# door-lock-pcb.net
KiCad netlist of a schematic drawn in EAGLE
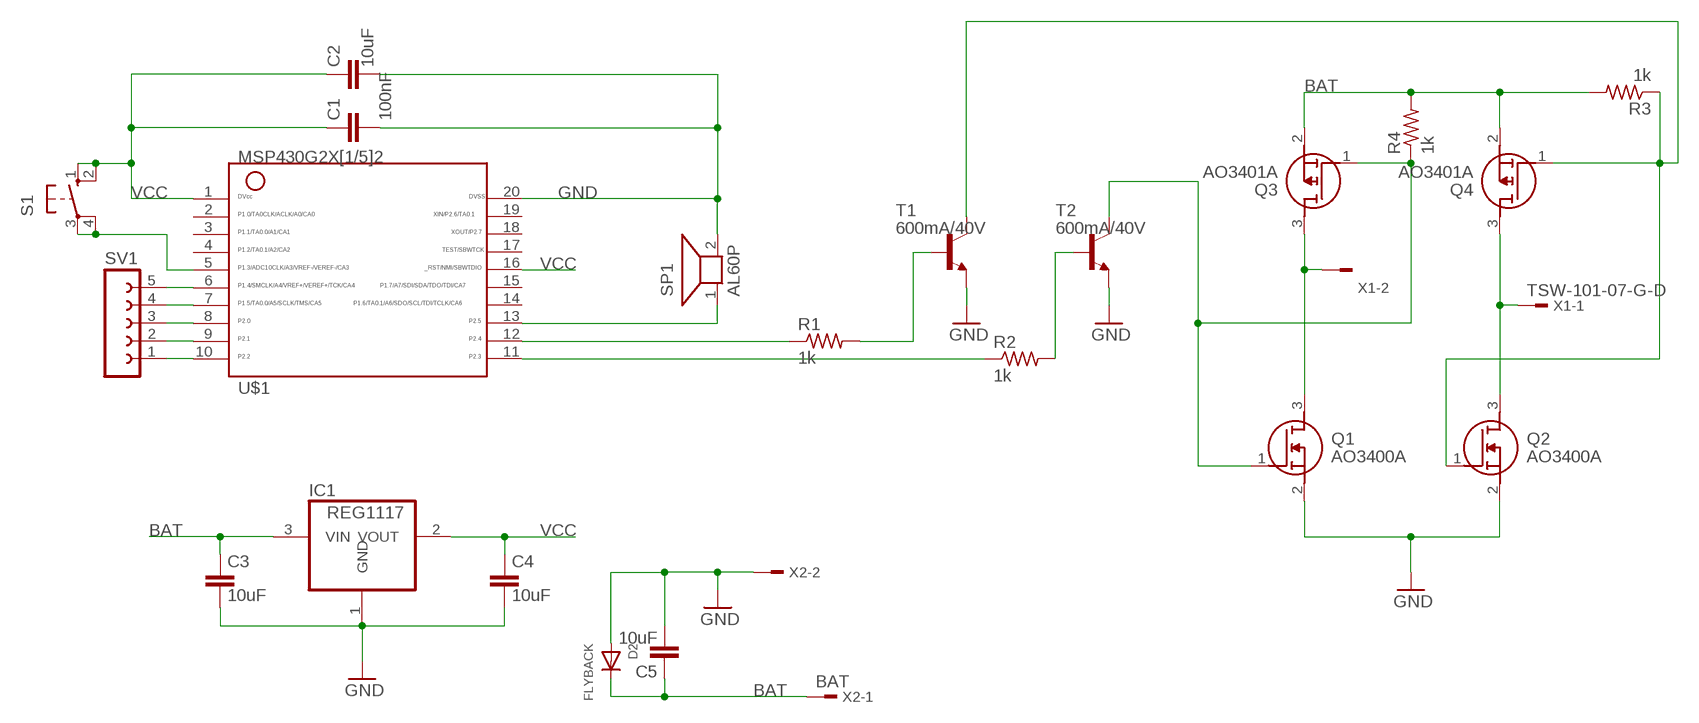
[diagram p0: schematic, sheet 1]

(export (version "E")
  (design (tool "Eeschema 10.0.6"))
  (components
    (comp (ref "C1")
      (value "100nF")
      (footprint "eagle-import:CAP_0805")
      (fields
        (field (name "DIGIKEY_PART_NUMBER") "311-1140-2-ND")
        (field (name "MANUFACTURER") "Yageo")
        (field (name "MPN") "CC0805KRX7R9BB104")
        (field (name "CREATED_BY") "PCBLayout.com")
      )
      (libsource (lib "eagle-import") (part "CC0805KRX7R9BB104"))
    )
    (comp (ref "C2")
      (value "10uF")
      (footprint "eagle-import:CAP_0805")
      (fields
        (field (name "DIGIKEY_PART_NUMBER") "311-1140-2-ND")
        (field (name "MANUFACTURER") "Yageo")
        (field (name "MPN") "CC0805KRX7R9BB104")
        (field (name "CREATED_BY") "PCBLayout.com")
      )
      (libsource (lib "eagle-import") (part "CC0805KRX7R9BB104"))
    )
    (comp (ref "C3")
      (value "10uF")
      (footprint "eagle-import:CAP_0805")
      (fields
        (field (name "DIGIKEY_PART_NUMBER") "311-1140-2-ND")
        (field (name "MANUFACTURER") "Yageo")
        (field (name "MPN") "CC0805KRX7R9BB104")
        (field (name "CREATED_BY") "PCBLayout.com")
      )
      (libsource (lib "eagle-import") (part "CC0805KRX7R9BB104"))
    )
    (comp (ref "C4")
      (value "10uF")
      (footprint "eagle-import:CAP_0805")
      (fields
        (field (name "DIGIKEY_PART_NUMBER") "311-1140-2-ND")
        (field (name "MANUFACTURER") "Yageo")
        (field (name "MPN") "CC0805KRX7R9BB104")
        (field (name "CREATED_BY") "PCBLayout.com")
      )
      (libsource (lib "eagle-import") (part "CC0805KRX7R9BB104"))
    )
    (comp (ref "C5")
      (value "10uF")
      (footprint "eagle-import:CAP_0805")
      (fields
        (field (name "DIGIKEY_PART_NUMBER") "311-1140-2-ND")
        (field (name "MANUFACTURER") "Yageo")
        (field (name "MPN") "CC0805KRX7R9BB104")
        (field (name "CREATED_BY") "PCBLayout.com")
      )
      (libsource (lib "eagle-import") (part "CC0805KRX7R9BB104"))
    )
    (comp (ref "D2")
      (value "FLYBACK")
      (footprint "eagle-import:SOD-523")
      (libsource (lib "eagle-import") (part "DIODESOD-523"))
    )
    (comp (ref "IC1")
      (value "REG1117")
      (footprint "eagle-import:SOT223")
      (libsource (lib "eagle-import") (part "REG1117"))
    )
    (comp (ref "Q1")
      (value "AO3400A")
      (footprint "eagle-import:SOT95P280X125-3N")
      (libsource (lib "eagle-import") (part "AO3400A"))
    )
    (comp (ref "Q2")
      (value "AO3400A")
      (footprint "eagle-import:SOT95P280X125-3N")
      (libsource (lib "eagle-import") (part "AO3400A"))
    )
    (comp (ref "Q3")
      (value "AO3401A")
      (footprint "eagle-import:SOT95P280X125-3N")
      (libsource (lib "eagle-import") (part "AO3401A"))
    )
    (comp (ref "Q4")
      (value "AO3401A")
      (footprint "eagle-import:SOT95P280X125-3N")
      (libsource (lib "eagle-import") (part "AO3401A"))
    )
    (comp (ref "R1")
      (value "1k")
      (footprint "eagle-import:RES_0805")
      (fields
        (field (name "DIGIKEY_PART_NUMBER") "541-0.0ATR-ND")
        (field (name "MANUFACTURER") "Vishay Dale")
        (field (name "MPN") "CRCW08050000Z0EA")
        (field (name "CREATED_BY") "PCBLayout.com")
      )
      (libsource (lib "eagle-import") (part "CRCW08050000Z0EA"))
    )
    (comp (ref "R2")
      (value "1k")
      (footprint "eagle-import:RES_0805")
      (fields
        (field (name "DIGIKEY_PART_NUMBER") "541-0.0ATR-ND")
        (field (name "MANUFACTURER") "Vishay Dale")
        (field (name "MPN") "CRCW08050000Z0EA")
        (field (name "CREATED_BY") "PCBLayout.com")
      )
      (libsource (lib "eagle-import") (part "CRCW08050000Z0EA"))
    )
    (comp (ref "R3")
      (value "1k")
      (footprint "eagle-import:RES_0805")
      (fields
        (field (name "DIGIKEY_PART_NUMBER") "541-0.0ATR-ND")
        (field (name "MANUFACTURER") "Vishay Dale")
        (field (name "MPN") "CRCW08050000Z0EA")
        (field (name "CREATED_BY") "PCBLayout.com")
      )
      (libsource (lib "eagle-import") (part "CRCW08050000Z0EA"))
    )
    (comp (ref "R4")
      (value "1k")
      (footprint "eagle-import:RES_0805")
      (fields
        (field (name "DIGIKEY_PART_NUMBER") "541-0.0ATR-ND")
        (field (name "MANUFACTURER") "Vishay Dale")
        (field (name "MPN") "CRCW08050000Z0EA")
        (field (name "CREATED_BY") "PCBLayout.com")
      )
      (libsource (lib "eagle-import") (part "CRCW08050000Z0EA"))
    )
    (comp (ref "S1")
      (value "10-XX")
      (footprint "eagle-import:B3F-10XX")
      (fields (field (name "MPN") "B3F-1000"))
      (libsource (lib "eagle-import") (part "10-XX"))
    )
    (comp (ref "SP1")
      (value "AL60P")
      (footprint "eagle-import:AL60P")
      (libsource (lib "eagle-import") (part "AL60P"))
    )
    (comp (ref "SV1")
      (value "FE05-1")
      (footprint "eagle-import:FE05-1")
      (libsource (lib "eagle-import") (part "FE05-1"))
    )
    (comp (ref "T1")
      (value "600mA/40V")
      (footprint "eagle-import:SOT23-3")
      (libsource (lib "eagle-import") (part "TRANS_NPN-MMBT2222AL"))
    )
    (comp (ref "T2")
      (value "600mA/40V")
      (footprint "eagle-import:SOT23-3")
      (libsource (lib "eagle-import") (part "TRANS_NPN-MMBT2222AL"))
    )
    (comp (ref "U$1")
      (value "G2X[1/5]2---N20")
      (footprint "eagle-import:N20")
      (libsource (lib "eagle-import") (part "G2X[1/5]2---N20"))
    )
    (comp (ref "X1")
      (value "TSW-101-07-G-D")
      (footprint "eagle-import:TSW-101-XX-G-D")
      (fields (field (name "MF") "Samtec Inc."))
      (libsource (lib "eagle-import") (part "TSW-101--G-D07"))
    )
    (comp (ref "X2")
      (value "BAT")
      (footprint "eagle-import:TSW-101-XX-G-D")
      (fields (field (name "MF") "Samtec Inc.") (field (name "MPN") "TSW-101-07-G-D"))
      (libsource (lib "eagle-import") (part "TSW-101--G-D07"))
    )
  )
  (nets
    (net (code "1") (name "/BAT") (class "Default")
      (node (ref "C3") (pin "1") (pinfunction "1_1") (pintype "passive"))
      (node (ref "C5") (pin "1") (pinfunction "1_1") (pintype "passive"))
      (node (ref "D2") (pin "K") (pinfunction "C_K") (pintype "passive"))
      (node (ref "IC1") (pin "3") (pinfunction "VIN_3") (pintype "input"))
      (node (ref "Q3") (pin "2") (pinfunction "S_2") (pintype "bidirectional"))
      (node (ref "Q4") (pin "2") (pinfunction "S_2") (pintype "bidirectional"))
      (node (ref "R3") (pin "2") (pinfunction "2_2") (pintype "passive"))
      (node (ref "R4") (pin "2") (pinfunction "2_2") (pintype "passive"))
      (node (ref "X2") (pin "1") (pinfunction "1_1") (pintype "passive"))
    )
    (net (code "2") (name "/VCC") (class "Default")
      (node (ref "C1") (pin "1") (pinfunction "1_1") (pintype "passive"))
      (node (ref "C2") (pin "1") (pinfunction "1_1") (pintype "passive"))
      (node (ref "C4") (pin "1") (pinfunction "1_1") (pintype "passive"))
      (node (ref "IC1") (pin "2") (pinfunction "VOUT_2") (pintype "output"))
      (node (ref "S1") (pin "1") (pinfunction "S_1") (pintype "passive"))
      (node (ref "S1") (pin "2") (pinfunction "S1_2") (pintype "passive"))
      (node (ref "U$1") (pin "1") (pinfunction "1_1") (pintype "bidirectional"))
      (node (ref "U$1") (pin "16") (pinfunction "16_16") (pintype "bidirectional"))
    )
    (net (code "3") (name "GND") (class "Default")
      (node (ref "C1") (pin "2") (pinfunction "2_2") (pintype "passive"))
      (node (ref "C2") (pin "2") (pinfunction "2_2") (pintype "passive"))
      (node (ref "C3") (pin "2") (pinfunction "2_2") (pintype "passive"))
      (node (ref "C4") (pin "2") (pinfunction "2_2") (pintype "passive"))
      (node (ref "C5") (pin "2") (pinfunction "2_2") (pintype "passive"))
      (node (ref "D2") (pin "A") (pinfunction "A_A") (pintype "passive"))
      (node (ref "IC1") (pin "1") (pinfunction "GND_1") (pintype "power_in"))
      (node (ref "Q1") (pin "2") (pinfunction "S_2") (pintype "bidirectional"))
      (node (ref "Q2") (pin "2") (pinfunction "S_2") (pintype "bidirectional"))
      (node (ref "SP1") (pin "2") (pinfunction "2_2") (pintype "passive"))
      (node (ref "T1") (pin "2") (pinfunction "E_2") (pintype "passive"))
      (node (ref "T2") (pin "2") (pinfunction "E_2") (pintype "passive"))
      (node (ref "U$1") (pin "20") (pinfunction "20_20") (pintype "bidirectional"))
      (node (ref "X2") (pin "2") (pinfunction "1_2") (pintype "passive"))
    )
    (net (code "4") (name "Net-(Q1-D)") (class "Default")
      (node (ref "Q1") (pin "3") (pinfunction "D_3") (pintype "bidirectional"))
      (node (ref "Q3") (pin "3") (pinfunction "D_3") (pintype "bidirectional"))
      (node (ref "X1") (pin "2") (pinfunction "1_2") (pintype "passive"))
    )
    (net (code "5") (name "Net-(Q1-G)") (class "Default")
      (node (ref "Q1") (pin "1") (pinfunction "G_1") (pintype "bidirectional"))
      (node (ref "Q3") (pin "1") (pinfunction "G_1") (pintype "bidirectional"))
      (node (ref "R4") (pin "1") (pinfunction "1_1") (pintype "passive"))
      (node (ref "T2") (pin "3") (pinfunction "C_3") (pintype "passive"))
    )
    (net (code "6") (name "Net-(Q2-D)") (class "Default")
      (node (ref "Q2") (pin "3") (pinfunction "D_3") (pintype "bidirectional"))
      (node (ref "Q4") (pin "3") (pinfunction "D_3") (pintype "bidirectional"))
      (node (ref "X1") (pin "1") (pinfunction "1_1") (pintype "passive"))
    )
    (net (code "7") (name "Net-(Q2-G)") (class "Default")
      (node (ref "Q2") (pin "1") (pinfunction "G_1") (pintype "bidirectional"))
      (node (ref "Q4") (pin "1") (pinfunction "G_1") (pintype "bidirectional"))
      (node (ref "R3") (pin "1") (pinfunction "1_1") (pintype "passive"))
      (node (ref "T1") (pin "3") (pinfunction "C_3") (pintype "passive"))
    )
    (net (code "8") (name "Net-(R1-Pad1)") (class "Default")
      (node (ref "R1") (pin "1") (pinfunction "1_1") (pintype "passive"))
      (node (ref "U$1") (pin "12") (pinfunction "12_12") (pintype "bidirectional"))
    )
    (net (code "9") (name "Net-(R2-Pad1)") (class "Default")
      (node (ref "R2") (pin "1") (pinfunction "1_1") (pintype "passive"))
      (node (ref "U$1") (pin "11") (pinfunction "11_11") (pintype "bidirectional"))
    )
    (net (code "10") (name "Net-(S1-P)") (class "Default")
      (node (ref "S1") (pin "3") (pinfunction "P_3") (pintype "passive"))
      (node (ref "S1") (pin "4") (pinfunction "P1_4") (pintype "passive"))
      (node (ref "U$1") (pin "5") (pinfunction "5_5") (pintype "bidirectional"))
    )
    (net (code "11") (name "Net-(SP1-Pad1)") (class "Default")
      (node (ref "SP1") (pin "1") (pinfunction "1_1") (pintype "passive"))
      (node (ref "U$1") (pin "13") (pinfunction "13_13") (pintype "bidirectional"))
    )
    (net (code "12") (name "Net-(SV1-Pad1)") (class "Default")
      (node (ref "SV1") (pin "1") (pinfunction "1_1") (pintype "passive"))
      (node (ref "U$1") (pin "10") (pinfunction "10_10") (pintype "bidirectional"))
    )
    (net (code "13") (name "Net-(SV1-Pad2)") (class "Default")
      (node (ref "SV1") (pin "2") (pinfunction "2_2") (pintype "passive"))
      (node (ref "U$1") (pin "9") (pinfunction "9_9") (pintype "bidirectional"))
    )
    (net (code "14") (name "Net-(SV1-Pad3)") (class "Default")
      (node (ref "SV1") (pin "3") (pinfunction "3_3") (pintype "passive"))
      (node (ref "U$1") (pin "8") (pinfunction "8_8") (pintype "bidirectional"))
    )
    (net (code "15") (name "Net-(SV1-Pad4)") (class "Default")
      (node (ref "SV1") (pin "4") (pinfunction "4_4") (pintype "passive"))
      (node (ref "U$1") (pin "7") (pinfunction "7_7") (pintype "bidirectional"))
    )
    (net (code "16") (name "Net-(SV1-Pad5)") (class "Default")
      (node (ref "SV1") (pin "5") (pinfunction "5_5") (pintype "passive"))
      (node (ref "U$1") (pin "6") (pinfunction "6_6") (pintype "bidirectional"))
    )
    (net (code "17") (name "Net-(T1-B)") (class "Default")
      (node (ref "R1") (pin "2") (pinfunction "2_2") (pintype "passive"))
      (node (ref "T1") (pin "1") (pinfunction "B_1") (pintype "passive"))
    )
    (net (code "18") (name "Net-(T2-B)") (class "Default")
      (node (ref "R2") (pin "2") (pinfunction "2_2") (pintype "passive"))
      (node (ref "T2") (pin "1") (pinfunction "B_1") (pintype "passive"))
    )
    (net (code "19") (name "unconnected-(U$1-Pad2)") (class "Default")
      (node (ref "U$1") (pin "2") (pinfunction "2_2") (pintype "bidirectional"))
    )
    (net (code "20") (name "unconnected-(U$1-Pad3)") (class "Default")
      (node (ref "U$1") (pin "3") (pinfunction "3_3") (pintype "bidirectional"))
    )
    (net (code "21") (name "unconnected-(U$1-Pad4)") (class "Default")
      (node (ref "U$1") (pin "4") (pinfunction "4_4") (pintype "bidirectional"))
    )
    (net (code "22") (name "unconnected-(U$1-Pad14)") (class "Default")
      (node (ref "U$1") (pin "14") (pinfunction "14_14") (pintype "bidirectional"))
    )
    (net (code "23") (name "unconnected-(U$1-Pad15)") (class "Default")
      (node (ref "U$1") (pin "15") (pinfunction "15_15") (pintype "bidirectional"))
    )
    (net (code "24") (name "unconnected-(U$1-Pad17)") (class "Default")
      (node (ref "U$1") (pin "17") (pinfunction "17_17") (pintype "bidirectional"))
    )
    (net (code "25") (name "unconnected-(U$1-Pad18)") (class "Default")
      (node (ref "U$1") (pin "18") (pinfunction "18_18") (pintype "bidirectional"))
    )
    (net (code "26") (name "unconnected-(U$1-Pad19)") (class "Default")
      (node (ref "U$1") (pin "19") (pinfunction "19_19") (pintype "bidirectional"))
    )
  )
)
